# Motor_Drive.net
KiCad netlist of a schematic drawn in Altium Designer
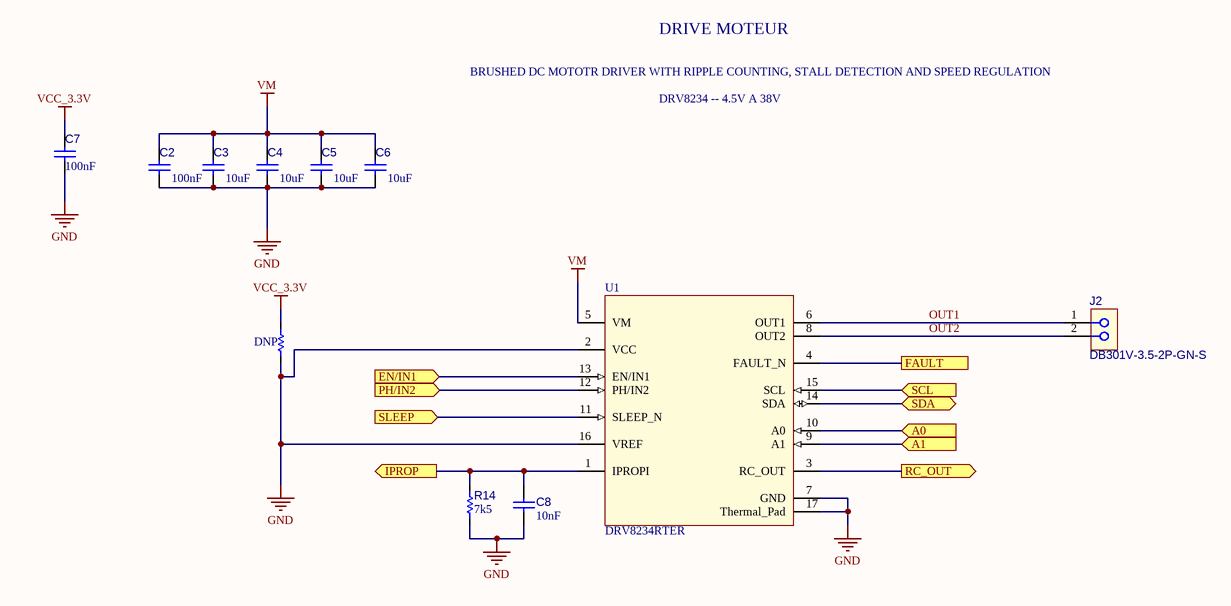
[diagram p0: Motor_Drive.SchDoc]

(export (version "E")
  (design (tool "Eeschema 10.0.6"))
  (components
    (comp (ref "C2")
      (value "100nF")
      (footprint "243-436-MikoBus-DrvMot:C_2012[0805]")
      (description "Capacitor type 1")
      (fields (field (name "TOLERANCE") "10%") (field (name "Comment") "CAP CER 100nF 50V 0805"))
      (libsource (lib "243-436-MikoBus-DrvMot") (part "capacitor"))
    )
    (comp (ref "C3")
      (value "10uF")
      (footprint "243-436-MikoBus-DrvMot:C_2012[0805]")
      (description "Capacitor type 1")
      (fields (field (name "TOLERANCE") "10%") (field (name "Comment") "CAP CER 10uF 10V X7R 0805"))
      (libsource (lib "243-436-MikoBus-DrvMot") (part "capacitor"))
    )
    (comp (ref "C4")
      (value "10uF")
      (footprint "243-436-MikoBus-DrvMot:C_2012[0805]")
      (description "Capacitor type 1")
      (fields (field (name "TOLERANCE") "10%") (field (name "Comment") "CAP CER 10uF 10V X7R 0805"))
      (libsource (lib "243-436-MikoBus-DrvMot") (part "capacitor"))
    )
    (comp (ref "C5")
      (value "10uF")
      (footprint "243-436-MikoBus-DrvMot:C_2012[0805]")
      (description "Capacitor type 1")
      (fields (field (name "TOLERANCE") "10%") (field (name "Comment") "CAP CER 10uF 10V X7R 0805"))
      (libsource (lib "243-436-MikoBus-DrvMot") (part "capacitor"))
    )
    (comp (ref "C6")
      (value "10uF")
      (footprint "243-436-MikoBus-DrvMot:C_2012[0805]")
      (description "Capacitor type 1")
      (fields (field (name "TOLERANCE") "10%") (field (name "Comment") "CAP CER 10uF 10V X7R 0805"))
      (libsource (lib "243-436-MikoBus-DrvMot") (part "capacitor"))
    )
    (comp (ref "C7")
      (value "100nF")
      (footprint "243-436-MikoBus-DrvMot:C_2012[0805]")
      (description "Capacitor type 1")
      (fields (field (name "TOLERANCE") "10%") (field (name "Comment") "CAP CER 100nF 50V 0805"))
      (libsource (lib "243-436-MikoBus-DrvMot") (part "capacitor"))
    )
    (comp (ref "C8")
      (value "10nF")
      (footprint "C_1005[0402]")
      (description "Capacitor type 1")
      (fields (field (name "TOLERANCE") "10%") (field (name "Comment") "CAP CER 10nF 50V X7R 0402"))
      (libsource (lib "243-436-MikoBus-DrvMot") (part "CAP017"))
    )
    (comp (ref "J2")
      (value "DB301V-3.5-2P-GN-S")
      (footprint "CONN_TERM_BLOCK_2POS_3mm5")
      (description "CONN TERM BLOCK 2POS 3.5mm pitch")
      (libsource (lib "TEP_243-AltiumLIB-Conn-TP-MH") (part "CONN-3MM5-2POS-TERM-BLOCK"))
    )
    (comp (ref "R14")
      (value "7k5")
      (footprint "R_1005[0402]")
      (description "Resistor type 1")
      (fields (field (name "TOLERANCE") "1%") (field (name "Comment") "Res 7k5 1% 0402"))
      (libsource (lib "243-436-MikoBus-DrvMot") (part "resistor"))
    )
    (comp (ref "r2000")
      (value "DNP")
      (footprint "R_1005[0402]")
      (description "Resistor type 1")
      (fields (field (name "TOLERANCE") "1%") (field (name "Comment") "Res 2k2 1% 0402"))
      (libsource (lib "243-436-MikoBus-DrvMot") (part "resistor"))
    )
    (comp (ref "U1")
      (value "DRV8234RTER")
      (footprint "U_WQFN50P300X300-16")
      (libsource (lib "TEP_243-Altium_Library") (part "U_DRV8234"))
    )
  )
  (nets
    (net (code "1") (name "/A0") (class "Default")
      (node (ref "U1") (pin "10") (pinfunction "A0_10") (pintype "input"))
    )
    (net (code "2") (name "/A1") (class "Default")
      (node (ref "U1") (pin "9") (pinfunction "A1_9") (pintype "input"))
    )
    (net (code "3") (name "/EN{slash}IN1") (class "Default")
      (node (ref "U1") (pin "13") (pinfunction "EN/IN1_13") (pintype "input"))
    )
    (net (code "4") (name "/FAULT") (class "Default")
      (node (ref "U1") (pin "4") (pinfunction "FAULT_N_4") (pintype "open_collector"))
    )
    (net (code "5") (name "/IPROP") (class "Default")
      (node (ref "C8") (pin "2") (pinfunction "2_2") (pintype "passive"))
      (node (ref "R14") (pin "2") (pinfunction "2_2") (pintype "passive"))
      (node (ref "U1") (pin "1") (pinfunction "IPROPI_1") (pintype "passive"))
    )
    (net (code "6") (name "/OUT1") (class "Default")
      (node (ref "J2") (pin "1") (pinfunction "1_1") (pintype "passive"))
      (node (ref "U1") (pin "6") (pinfunction "OUT1_6") (pintype "passive"))
    )
    (net (code "7") (name "/OUT2") (class "Default")
      (node (ref "J2") (pin "2") (pinfunction "2_2") (pintype "passive"))
      (node (ref "U1") (pin "8") (pinfunction "OUT2_8") (pintype "passive"))
    )
    (net (code "8") (name "/PH{slash}IN2") (class "Default")
      (node (ref "U1") (pin "12") (pinfunction "PH/IN2_12") (pintype "input"))
    )
    (net (code "9") (name "/RC_OUT") (class "Default")
      (node (ref "U1") (pin "3") (pinfunction "RC_OUT_3") (pintype "open_collector"))
    )
    (net (code "10") (name "/SCL") (class "Default")
      (node (ref "U1") (pin "15") (pinfunction "SCL_15") (pintype "input"))
    )
    (net (code "11") (name "/SDA") (class "Default")
      (node (ref "U1") (pin "14") (pinfunction "SDA_14") (pintype "bidirectional"))
    )
    (net (code "12") (name "/SLEEP") (class "Default")
      (node (ref "U1") (pin "11") (pinfunction "SLEEP_N_11") (pintype "input"))
    )
    (net (code "13") (name "GND") (class "Default")
      (node (ref "C2") (pin "1") (pinfunction "1_1") (pintype "passive"))
      (node (ref "C3") (pin "1") (pinfunction "1_1") (pintype "passive"))
      (node (ref "C4") (pin "2") (pinfunction "2_2") (pintype "passive"))
      (node (ref "C5") (pin "1") (pinfunction "1_1") (pintype "passive"))
      (node (ref "C6") (pin "2") (pinfunction "2_2") (pintype "passive"))
      (node (ref "C7") (pin "1") (pinfunction "1_1") (pintype "passive"))
      (node (ref "C8") (pin "1") (pinfunction "1_1") (pintype "passive"))
      (node (ref "R14") (pin "1") (pinfunction "1_1") (pintype "passive"))
      (node (ref "U1") (pin "16") (pinfunction "VREF_16") (pintype "passive"))
      (node (ref "U1") (pin "17") (pinfunction "Thermal_Pad_17") (pintype "power_in"))
      (node (ref "U1") (pin "2") (pinfunction "VCC_2") (pintype "power_in"))
      (node (ref "U1") (pin "7") (pinfunction "GND_7") (pintype "power_in"))
      (node (ref "r2000") (pin "1") (pinfunction "1_1") (pintype "passive"))
    )
    (net (code "14") (name "VCC_3.3V") (class "Default")
      (node (ref "C7") (pin "2") (pinfunction "2_2") (pintype "passive"))
      (node (ref "r2000") (pin "2") (pinfunction "2_2") (pintype "passive"))
    )
    (net (code "15") (name "VM") (class "Default")
      (node (ref "C2") (pin "2") (pinfunction "2_2") (pintype "passive"))
      (node (ref "C3") (pin "2") (pinfunction "2_2") (pintype "passive"))
      (node (ref "C4") (pin "1") (pinfunction "1_1") (pintype "passive"))
      (node (ref "C5") (pin "2") (pinfunction "2_2") (pintype "passive"))
      (node (ref "C6") (pin "1") (pinfunction "1_1") (pintype "passive"))
      (node (ref "U1") (pin "5") (pinfunction "VM_5") (pintype "power_in"))
    )
  )
)
